# schema.net
KiCad netlist of a schematic drawn in EAGLE
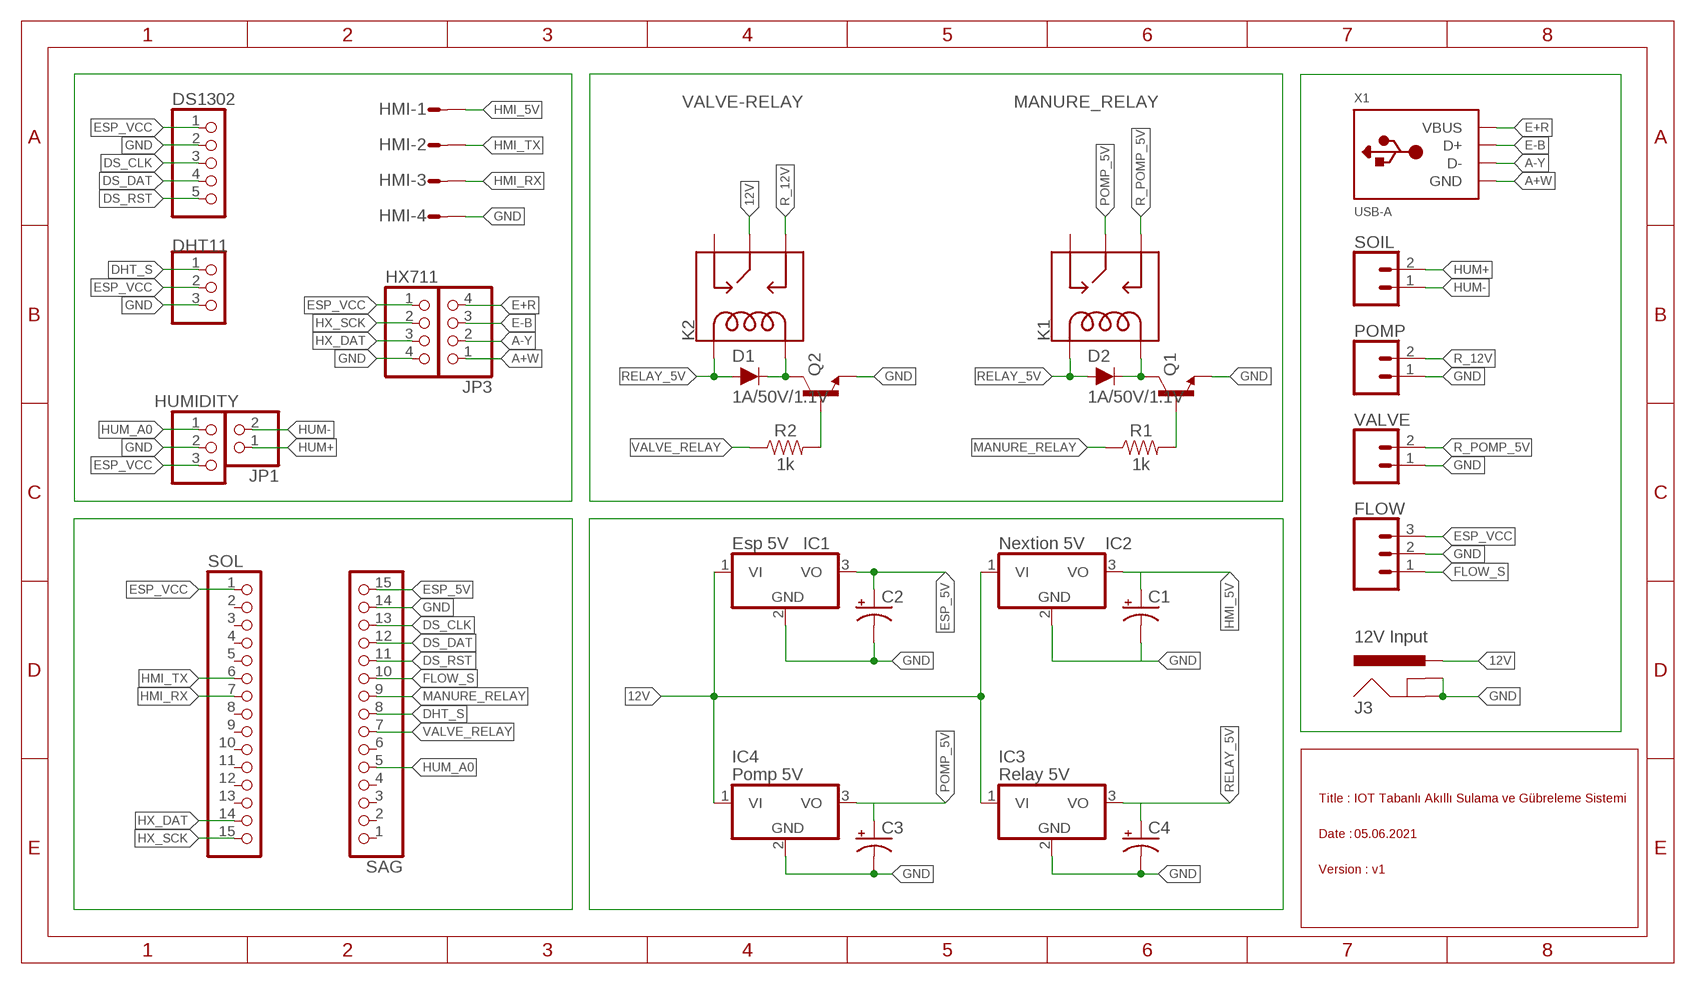
[diagram p0: schematic, sheet 1]

(export (version "E")
  (design (tool "Eeschema 10.0.6"))
  (components
    (comp (ref "C1")
      (value "CPOL-USE5-5")
      (footprint "eagle-import:E5-5")
      (libsource (lib "eagle-import") (part "CPOL-USE5-5"))
    )
    (comp (ref "C2")
      (value "CPOL-USE5-5")
      (footprint "eagle-import:E5-5")
      (libsource (lib "eagle-import") (part "CPOL-USE5-5"))
    )
    (comp (ref "C3")
      (value "CPOL-USE5-5")
      (footprint "eagle-import:E5-5")
      (libsource (lib "eagle-import") (part "CPOL-USE5-5"))
    )
    (comp (ref "C4")
      (value "CPOL-USE5-5")
      (footprint "eagle-import:E5-5")
      (libsource (lib "eagle-import") (part "CPOL-USE5-5"))
    )
    (comp (ref "D1")
      (value "1A/50V/1.1V")
      (footprint "eagle-import:DIODE-1N4001")
      (libsource (lib "eagle-import") (part "DIODE-PTH"))
    )
    (comp (ref "D2")
      (value "1A/50V/1.1V")
      (footprint "eagle-import:DIODE-1N4001")
      (libsource (lib "eagle-import") (part "DIODE-PTH"))
    )
    (comp (ref "DHT11")
      (value "DHT11")
      (footprint "eagle-import:1X03")
      (libsource (lib "eagle-import") (part "PINHD-1X3"))
    )
    (comp (ref "DS1302")
      (value "PINHD-1X5")
      (footprint "eagle-import:1X05")
      (libsource (lib "eagle-import") (part "PINHD-1X5"))
    )
    (comp (ref "FLOW")
      (value "CONN_03JST-PTH")
      (footprint "eagle-import:JST-3-PTH")
      (libsource (lib "eagle-import") (part "CONN_03JST-PTH"))
    )
    (comp (ref "HMI")
      (value "L04P")
      (footprint "eagle-import:L04P")
      (libsource (lib "eagle-import") (part "L04P"))
    )
    (comp (ref "HUMIDITY")
      (value "PINHD-1X3")
      (footprint "eagle-import:1X03")
      (libsource (lib "eagle-import") (part "PINHD-1X3"))
    )
    (comp (ref "HX711")
      (value "PINHD-1X4")
      (footprint "eagle-import:1X04")
      (libsource (lib "eagle-import") (part "PINHD-1X4"))
    )
    (comp (ref "IC1")
      (value "Esp 5V")
      (footprint "eagle-import:TO220H")
      (libsource (lib "eagle-import") (part "78T15"))
    )
    (comp (ref "IC2")
      (value "Nextion 5V")
      (footprint "eagle-import:TO220H")
      (libsource (lib "eagle-import") (part "78T15"))
    )
    (comp (ref "IC3")
      (value "Relay 5V")
      (footprint "eagle-import:TO220H")
      (libsource (lib "eagle-import") (part "78T15"))
    )
    (comp (ref "IC4")
      (value "Pomp 5V")
      (footprint "eagle-import:TO220H")
      (libsource (lib "eagle-import") (part "78T15"))
    )
    (comp (ref "J3")
      (value "12V Input")
      (footprint "eagle-import:POWER_JACK_PTH_LOCK")
      (libsource (lib "eagle-import") (part "POWER_JACKPTH_LOCK"))
    )
    (comp (ref "JP1")
      (value "PINHD-1X2")
      (footprint "eagle-import:1X02")
      (libsource (lib "eagle-import") (part "PINHD-1X2"))
    )
    (comp (ref "JP3")
      (value "PINHD-1X4")
      (footprint "eagle-import:1X04")
      (libsource (lib "eagle-import") (part "PINHD-1X4"))
    )
    (comp (ref "K1")
      (value "MANURE_RELAY")
      (footprint "eagle-import:RELAY_G5LE")
      (libsource (lib "eagle-import") (part "RELAY-SPDT"))
    )
    (comp (ref "K2")
      (value "VALVE-RELAY")
      (footprint "eagle-import:RELAY_G5LE")
      (libsource (lib "eagle-import") (part "RELAY-SPDT"))
    )
    (comp (ref "POMP")
      (value "CONN_02-JST-2-PTH-NO_SILK")
      (footprint "eagle-import:JST-2-PTH-NS")
      (libsource (lib "eagle-import") (part "CONN_02-JST-2-PTH-NO_SILK"))
    )
    (comp (ref "Q1")
      (value "200mA/40V")
      (footprint "eagle-import:TO-92")
      (libsource (lib "eagle-import") (part "TRANS_NPN-2N3904"))
    )
    (comp (ref "Q2")
      (value "200mA/40V")
      (footprint "eagle-import:TO-92")
      (libsource (lib "eagle-import") (part "TRANS_NPN-2N3904"))
    )
    (comp (ref "R1")
      (value "1k")
      (footprint "eagle-import:AXIAL-0.3")
      (libsource (lib "eagle-import") (part "1KOHM-HORIZ-1/4W-1%"))
    )
    (comp (ref "R2")
      (value "1k")
      (footprint "eagle-import:AXIAL-0.3")
      (libsource (lib "eagle-import") (part "1KOHM-HORIZ-1/4W-1%"))
    )
    (comp (ref "SAG")
      (value "PINHD-1X15-CB")
      (footprint "eagle-import:1X15-CB")
      (libsource (lib "eagle-import") (part "PINHD-1X15-CB"))
    )
    (comp (ref "SOIL")
      (value "CONN_02-JST-2-PTH-NO_SILK")
      (footprint "eagle-import:JST-2-PTH-NS")
      (libsource (lib "eagle-import") (part "CONN_02-JST-2-PTH-NO_SILK"))
    )
    (comp (ref "SOL")
      (value "PINHD-1X15-CB")
      (footprint "eagle-import:1X15-CB")
      (libsource (lib "eagle-import") (part "PINHD-1X15-CB"))
    )
    (comp (ref "VALVE")
      (value "CONN_02-JST-2-PTH-NO_SILK")
      (footprint "eagle-import:JST-2-PTH-NS")
      (libsource (lib "eagle-import") (part "CONN_02-JST-2-PTH-NO_SILK"))
    )
    (comp (ref "X1")
      (value "USB-A")
      (footprint "eagle-import:MOLEX_480371000")
      (libsource (lib "eagle-import") (part "USB-A"))
    )
  )
  (nets
    (net (code "1") (name "12V") (class "Default")
      (node (ref "IC1") (pin "1") (pinfunction "VI_1") (pintype "input"))
      (node (ref "IC2") (pin "1") (pinfunction "VI_1") (pintype "input"))
      (node (ref "IC3") (pin "1") (pinfunction "VI_1") (pintype "input"))
      (node (ref "IC4") (pin "1") (pinfunction "VI_1") (pintype "input"))
      (node (ref "J3") (pin "PWR") (pinfunction "PWR_PWR") (pintype "bidirectional"))
      (node (ref "K2") (pin "1") (pinfunction "MAIN_1") (pintype "bidirectional"))
    )
    (net (code "2") (name "A+W") (class "Default")
      (node (ref "JP3") (pin "1") (pinfunction "1_1") (pintype "passive"))
      (node (ref "X1") (pin "4") (pinfunction "GND_4") (pintype "power_in"))
    )
    (net (code "3") (name "A-Y") (class "Default")
      (node (ref "JP3") (pin "2") (pinfunction "2_2") (pintype "passive"))
      (node (ref "X1") (pin "2") (pinfunction "D-_2") (pintype "bidirectional"))
    )
    (net (code "4") (name "DHT_S") (class "Default")
      (node (ref "DHT11") (pin "1") (pinfunction "1_1") (pintype "passive"))
      (node (ref "SAG") (pin "8") (pinfunction "8_8") (pintype "passive"))
    )
    (net (code "5") (name "DS_CLK") (class "Default")
      (node (ref "DS1302") (pin "3") (pinfunction "3_3") (pintype "passive"))
      (node (ref "SAG") (pin "13") (pinfunction "13_13") (pintype "passive"))
    )
    (net (code "6") (name "DS_DAT") (class "Default")
      (node (ref "DS1302") (pin "4") (pinfunction "4_4") (pintype "passive"))
      (node (ref "SAG") (pin "12") (pinfunction "12_12") (pintype "passive"))
    )
    (net (code "7") (name "DS_RST") (class "Default")
      (node (ref "DS1302") (pin "5") (pinfunction "5_5") (pintype "passive"))
      (node (ref "SAG") (pin "11") (pinfunction "11_11") (pintype "passive"))
    )
    (net (code "8") (name "E+R") (class "Default")
      (node (ref "JP3") (pin "4") (pinfunction "4_4") (pintype "passive"))
      (node (ref "X1") (pin "1") (pinfunction "VBUS_1") (pintype "power_in"))
    )
    (net (code "9") (name "E-B") (class "Default")
      (node (ref "JP3") (pin "3") (pinfunction "3_3") (pintype "passive"))
      (node (ref "X1") (pin "3") (pinfunction "D+_3") (pintype "bidirectional"))
    )
    (net (code "10") (name "ESP_5V") (class "Default")
      (node (ref "C2") (pin "+") (pinfunction "+_+") (pintype "passive"))
      (node (ref "IC1") (pin "3") (pinfunction "VO_3") (pintype "passive"))
      (node (ref "SAG") (pin "15") (pinfunction "15_15") (pintype "passive"))
    )
    (net (code "11") (name "ESP_VCC") (class "Default")
      (node (ref "DHT11") (pin "2") (pinfunction "2_2") (pintype "passive"))
      (node (ref "DS1302") (pin "1") (pinfunction "1_1") (pintype "passive"))
      (node (ref "FLOW") (pin "3") (pinfunction "3_3") (pintype "passive"))
      (node (ref "HUMIDITY") (pin "3") (pinfunction "3_3") (pintype "passive"))
      (node (ref "HX711") (pin "1") (pinfunction "1_1") (pintype "passive"))
      (node (ref "SOL") (pin "1") (pinfunction "1_1") (pintype "passive"))
    )
    (net (code "12") (name "FLOW_S") (class "Default")
      (node (ref "FLOW") (pin "1") (pinfunction "1_1") (pintype "passive"))
      (node (ref "SAG") (pin "10") (pinfunction "10_10") (pintype "passive"))
    )
    (net (code "13") (name "GND") (class "Default")
      (node (ref "C2") (pin "-") (pinfunction "-_-") (pintype "passive"))
      (node (ref "C3") (pin "-") (pinfunction "-_-") (pintype "passive"))
      (node (ref "C4") (pin "-") (pinfunction "-_-") (pintype "passive"))
      (node (ref "DHT11") (pin "3") (pinfunction "3_3") (pintype "passive"))
      (node (ref "DS1302") (pin "2") (pinfunction "2_2") (pintype "passive"))
      (node (ref "FLOW") (pin "2") (pinfunction "2_2") (pintype "passive"))
      (node (ref "HMI") (pin "4") (pinfunction "S_4") (pintype "passive"))
      (node (ref "HUMIDITY") (pin "2") (pinfunction "2_2") (pintype "passive"))
      (node (ref "HX711") (pin "4") (pinfunction "4_4") (pintype "passive"))
      (node (ref "IC1") (pin "2") (pinfunction "GND_2") (pintype "passive"))
      (node (ref "IC2") (pin "2") (pinfunction "GND_2") (pintype "passive"))
      (node (ref "IC3") (pin "2") (pinfunction "GND_2") (pintype "passive"))
      (node (ref "IC4") (pin "2") (pinfunction "GND_2") (pintype "passive"))
      (node (ref "J3") (pin "GND") (pinfunction "GND_GND") (pintype "bidirectional"))
      (node (ref "J3") (pin "GNDBREAK") (pinfunction "GNDBREAK_GNDBREAK") (pintype "bidirectional"))
      (node (ref "POMP") (pin "1") (pinfunction "1_1") (pintype "passive"))
      (node (ref "Q1") (pin "1") (pinfunction "E_1") (pintype "passive"))
      (node (ref "Q2") (pin "1") (pinfunction "E_1") (pintype "passive"))
      (node (ref "SAG") (pin "14") (pinfunction "14_14") (pintype "passive"))
      (node (ref "VALVE") (pin "1") (pinfunction "1_1") (pintype "passive"))
    )
    (net (code "14") (name "HMI_5V") (class "Default")
      (node (ref "HMI") (pin "1") (pinfunction "S_1") (pintype "passive"))
      (node (ref "IC2") (pin "3") (pinfunction "VO_3") (pintype "passive"))
    )
    (net (code "15") (name "HMI_RX") (class "Default")
      (node (ref "HMI") (pin "3") (pinfunction "S_3") (pintype "passive"))
      (node (ref "SOL") (pin "7") (pinfunction "7_7") (pintype "passive"))
    )
    (net (code "16") (name "HMI_TX") (class "Default")
      (node (ref "HMI") (pin "2") (pinfunction "S_2") (pintype "passive"))
      (node (ref "SOL") (pin "6") (pinfunction "6_6") (pintype "passive"))
    )
    (net (code "17") (name "HUM+") (class "Default")
      (node (ref "JP1") (pin "1") (pinfunction "1_1") (pintype "passive"))
      (node (ref "SOIL") (pin "2") (pinfunction "2_2") (pintype "passive"))
    )
    (net (code "18") (name "HUM-") (class "Default")
      (node (ref "JP1") (pin "2") (pinfunction "2_2") (pintype "passive"))
      (node (ref "SOIL") (pin "1") (pinfunction "1_1") (pintype "passive"))
    )
    (net (code "19") (name "HUM_A0") (class "Default")
      (node (ref "HUMIDITY") (pin "1") (pinfunction "1_1") (pintype "passive"))
      (node (ref "SAG") (pin "5") (pinfunction "5_5") (pintype "passive"))
    )
    (net (code "20") (name "HX_DAT") (class "Default")
      (node (ref "HX711") (pin "3") (pinfunction "3_3") (pintype "passive"))
      (node (ref "SOL") (pin "14") (pinfunction "14_14") (pintype "passive"))
    )
    (net (code "21") (name "HX_SCK") (class "Default")
      (node (ref "HX711") (pin "2") (pinfunction "2_2") (pintype "passive"))
      (node (ref "SOL") (pin "15") (pinfunction "15_15") (pintype "passive"))
    )
    (net (code "22") (name "MANURE_RELAY") (class "Default")
      (node (ref "R1") (pin "P$1") (pinfunction "1_P$1") (pintype "passive"))
      (node (ref "SAG") (pin "9") (pinfunction "9_9") (pintype "passive"))
    )
    (net (code "23") (name "Net-(K1-COIL2)") (class "Default")
      (node (ref "D2") (pin "C") (pinfunction "C_C") (pintype "passive"))
      (node (ref "K1") (pin "5") (pinfunction "COIL2_5") (pintype "bidirectional"))
      (node (ref "Q1") (pin "3") (pinfunction "C_3") (pintype "passive"))
    )
    (net (code "24") (name "Net-(K2-COIL2)") (class "Default")
      (node (ref "D1") (pin "C") (pinfunction "C_C") (pintype "passive"))
      (node (ref "K2") (pin "5") (pinfunction "COIL2_5") (pintype "bidirectional"))
      (node (ref "Q2") (pin "3") (pinfunction "C_3") (pintype "passive"))
    )
    (net (code "25") (name "Net-(Q1-B)") (class "Default")
      (node (ref "Q1") (pin "2") (pinfunction "B_2") (pintype "passive"))
      (node (ref "R1") (pin "P$2") (pinfunction "2_P$2") (pintype "passive"))
    )
    (net (code "26") (name "Net-(Q2-B)") (class "Default")
      (node (ref "Q2") (pin "2") (pinfunction "B_2") (pintype "passive"))
      (node (ref "R2") (pin "P$2") (pinfunction "2_P$2") (pintype "passive"))
    )
    (net (code "27") (name "POMP_5V") (class "Default")
      (node (ref "IC4") (pin "3") (pinfunction "VO_3") (pintype "passive"))
      (node (ref "K1") (pin "1") (pinfunction "MAIN_1") (pintype "bidirectional"))
    )
    (net (code "28") (name "RELAY_5V") (class "Default")
      (node (ref "D1") (pin "A") (pinfunction "A_A") (pintype "passive"))
      (node (ref "D2") (pin "A") (pinfunction "A_A") (pintype "passive"))
      (node (ref "IC3") (pin "3") (pinfunction "VO_3") (pintype "passive"))
      (node (ref "K1") (pin "2") (pinfunction "COIL1_2") (pintype "bidirectional"))
      (node (ref "K2") (pin "2") (pinfunction "COIL1_2") (pintype "bidirectional"))
    )
    (net (code "29") (name "R_12V") (class "Default")
      (node (ref "K2") (pin "3") (pinfunction "NO_3") (pintype "bidirectional"))
      (node (ref "POMP") (pin "2") (pinfunction "2_2") (pintype "passive"))
    )
    (net (code "30") (name "R_POMP_5V") (class "Default")
      (node (ref "K1") (pin "3") (pinfunction "NO_3") (pintype "bidirectional"))
      (node (ref "VALVE") (pin "2") (pinfunction "2_2") (pintype "passive"))
    )
    (net (code "31") (name "VALVE_RELAY") (class "Default")
      (node (ref "R2") (pin "P$1") (pinfunction "1_P$1") (pintype "passive"))
      (node (ref "SAG") (pin "7") (pinfunction "7_7") (pintype "passive"))
    )
    (net (code "32") (name "unconnected-(C1-Pad+)") (class "Default")
      (node (ref "C1") (pin "+") (pinfunction "+_+") (pintype "passive"))
    )
    (net (code "33") (name "unconnected-(C1-Pad-)") (class "Default")
      (node (ref "C1") (pin "-") (pinfunction "-_-") (pintype "passive"))
    )
    (net (code "34") (name "unconnected-(C3-Pad+)") (class "Default")
      (node (ref "C3") (pin "+") (pinfunction "+_+") (pintype "passive"))
    )
    (net (code "35") (name "unconnected-(C4-Pad+)") (class "Default")
      (node (ref "C4") (pin "+") (pinfunction "+_+") (pintype "passive"))
    )
    (net (code "36") (name "unconnected-(K1-NC-Pad4)") (class "Default")
      (node (ref "K1") (pin "4") (pinfunction "NC_4") (pintype "bidirectional"))
    )
    (net (code "37") (name "unconnected-(K2-NC-Pad4)") (class "Default")
      (node (ref "K2") (pin "4") (pinfunction "NC_4") (pintype "bidirectional"))
    )
    (net (code "38") (name "unconnected-(SAG-Pad1)") (class "Default")
      (node (ref "SAG") (pin "1") (pinfunction "1_1") (pintype "passive"))
    )
    (net (code "39") (name "unconnected-(SAG-Pad2)") (class "Default")
      (node (ref "SAG") (pin "2") (pinfunction "2_2") (pintype "passive"))
    )
    (net (code "40") (name "unconnected-(SAG-Pad3)") (class "Default")
      (node (ref "SAG") (pin "3") (pinfunction "3_3") (pintype "passive"))
    )
    (net (code "41") (name "unconnected-(SAG-Pad4)") (class "Default")
      (node (ref "SAG") (pin "4") (pinfunction "4_4") (pintype "passive"))
    )
    (net (code "42") (name "unconnected-(SAG-Pad6)") (class "Default")
      (node (ref "SAG") (pin "6") (pinfunction "6_6") (pintype "passive"))
    )
    (net (code "43") (name "unconnected-(SOL-Pad2)") (class "Default")
      (node (ref "SOL") (pin "2") (pinfunction "2_2") (pintype "passive"))
    )
    (net (code "44") (name "unconnected-(SOL-Pad3)") (class "Default")
      (node (ref "SOL") (pin "3") (pinfunction "3_3") (pintype "passive"))
    )
    (net (code "45") (name "unconnected-(SOL-Pad4)") (class "Default")
      (node (ref "SOL") (pin "4") (pinfunction "4_4") (pintype "passive"))
    )
    (net (code "46") (name "unconnected-(SOL-Pad5)") (class "Default")
      (node (ref "SOL") (pin "5") (pinfunction "5_5") (pintype "passive"))
    )
    (net (code "47") (name "unconnected-(SOL-Pad8)") (class "Default")
      (node (ref "SOL") (pin "8") (pinfunction "8_8") (pintype "passive"))
    )
    (net (code "48") (name "unconnected-(SOL-Pad9)") (class "Default")
      (node (ref "SOL") (pin "9") (pinfunction "9_9") (pintype "passive"))
    )
    (net (code "49") (name "unconnected-(SOL-Pad10)") (class "Default")
      (node (ref "SOL") (pin "10") (pinfunction "10_10") (pintype "passive"))
    )
    (net (code "50") (name "unconnected-(SOL-Pad11)") (class "Default")
      (node (ref "SOL") (pin "11") (pinfunction "11_11") (pintype "passive"))
    )
    (net (code "51") (name "unconnected-(SOL-Pad12)") (class "Default")
      (node (ref "SOL") (pin "12") (pinfunction "12_12") (pintype "passive"))
    )
    (net (code "52") (name "unconnected-(SOL-Pad13)") (class "Default")
      (node (ref "SOL") (pin "13") (pinfunction "13_13") (pintype "passive"))
    )
  )
)
